# Sitara_Power.net
KiCad netlist of a schematic drawn in Altium Designer
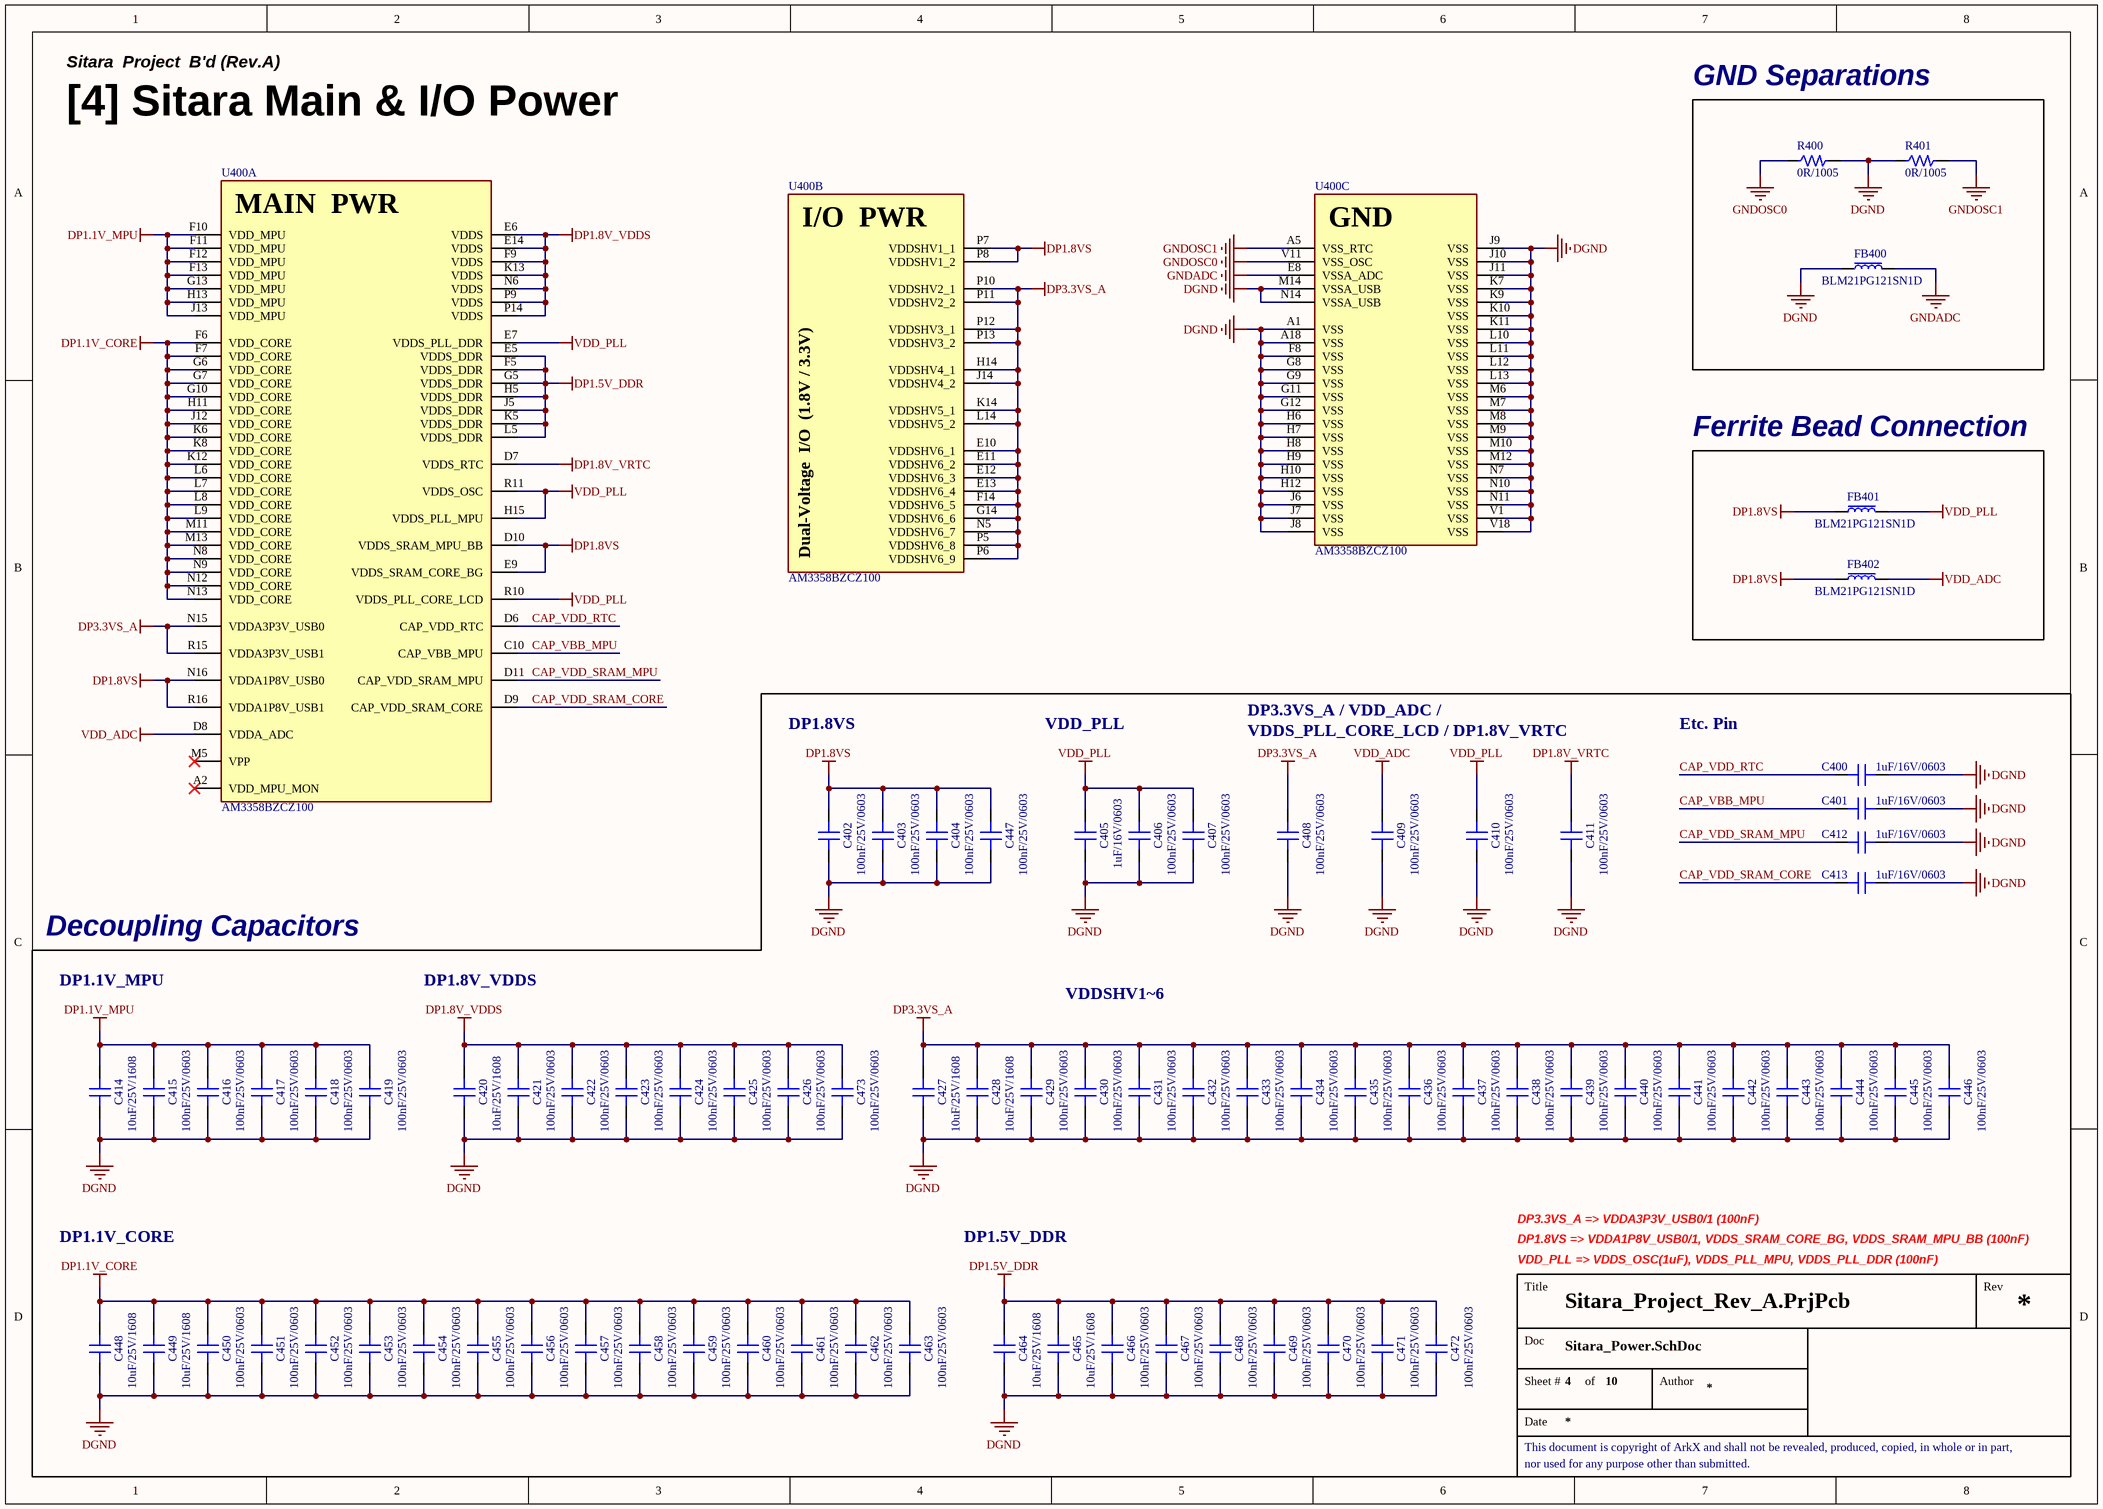
[diagram p0: Sitara_Power.SchDoc]

(export (version "E")
  (design (tool "Eeschema 10.0.6"))
  (components
    (comp (ref "C400")
      (value "1uF/16V/0603")
      (footprint "CAP 0603 (0201_INCH)")
      (description "Ceramic CAP_1uF/16V/0603")
      (fields (field (name "LCSC PART #") "C307385"))
      (libsource (lib "Arkx") (part "CAP_1uF/16V/0603"))
    )
    (comp (ref "C401")
      (value "1uF/16V/0603")
      (footprint "CAP 0603 (0201_INCH)")
      (description "Ceramic CAP_1uF/16V/0603")
      (fields (field (name "LCSC PART #") "C307385"))
      (libsource (lib "Arkx") (part "CAP_1uF/16V/0603"))
    )
    (comp (ref "C402")
      (value "100nF/25V/0603")
      (footprint "CAP 0603 (0201_INCH)")
      (description "Ceramic CAP_100nF/25V/0603")
      (fields (field (name "LCSC PART #") "C181047"))
      (libsource (lib "Arkx") (part "CAP_100nF/25V/0603"))
    )
    (comp (ref "C403")
      (value "100nF/25V/0603")
      (footprint "CAP 0603 (0201_INCH)")
      (description "Ceramic CAP_100nF/25V/0603")
      (fields (field (name "LCSC PART #") "C181047"))
      (libsource (lib "Arkx") (part "CAP_100nF/25V/0603"))
    )
    (comp (ref "C404")
      (value "100nF/25V/0603")
      (footprint "CAP 0603 (0201_INCH)")
      (description "Ceramic CAP_100nF/25V/0603")
      (fields (field (name "LCSC PART #") "C181047"))
      (libsource (lib "Arkx") (part "CAP_100nF/25V/0603"))
    )
    (comp (ref "C405")
      (value "1uF/16V/0603")
      (footprint "CAP 0603 (0201_INCH)")
      (description "Ceramic CAP_1uF/16V/0603")
      (fields (field (name "LCSC PART #") "C307385"))
      (libsource (lib "Arkx") (part "CAP_1uF/16V/0603"))
    )
    (comp (ref "C406")
      (value "100nF/25V/0603")
      (footprint "CAP 0603 (0201_INCH)")
      (description "Ceramic CAP_100nF/25V/0603")
      (fields (field (name "LCSC PART #") "C181047"))
      (libsource (lib "Arkx") (part "CAP_100nF/25V/0603"))
    )
    (comp (ref "C407")
      (value "100nF/25V/0603")
      (footprint "CAP 0603 (0201_INCH)")
      (description "Ceramic CAP_100nF/25V/0603")
      (fields (field (name "LCSC PART #") "C181047"))
      (libsource (lib "Arkx") (part "CAP_100nF/25V/0603"))
    )
    (comp (ref "C408")
      (value "100nF/25V/0603")
      (footprint "CAP 0603 (0201_INCH)")
      (description "Ceramic CAP_100nF/25V/0603")
      (fields (field (name "LCSC PART #") "C181047"))
      (libsource (lib "Arkx") (part "CAP_100nF/25V/0603"))
    )
    (comp (ref "C409")
      (value "100nF/25V/0603")
      (footprint "CAP 0603 (0201_INCH)")
      (description "Ceramic CAP_100nF/25V/0603")
      (fields (field (name "LCSC PART #") "C181047"))
      (libsource (lib "Arkx") (part "CAP_100nF/25V/0603"))
    )
    (comp (ref "C410")
      (value "100nF/25V/0603")
      (footprint "CAP 0603 (0201_INCH)")
      (description "Ceramic CAP_100nF/25V/0603")
      (fields (field (name "LCSC PART #") "C181047"))
      (libsource (lib "Arkx") (part "CAP_100nF/25V/0603"))
    )
    (comp (ref "C411")
      (value "100nF/25V/0603")
      (footprint "CAP 0603 (0201_INCH)")
      (description "Ceramic CAP_100nF/25V/0603")
      (fields (field (name "LCSC PART #") "C181047"))
      (libsource (lib "Arkx") (part "CAP_100nF/25V/0603"))
    )
    (comp (ref "C412")
      (value "1uF/16V/0603")
      (footprint "CAP 0603 (0201_INCH)")
      (description "Ceramic CAP_1uF/16V/0603")
      (fields (field (name "LCSC PART #") "C307385"))
      (libsource (lib "Arkx") (part "CAP_1uF/16V/0603"))
    )
    (comp (ref "C413")
      (value "1uF/16V/0603")
      (footprint "CAP 0603 (0201_INCH)")
      (description "Ceramic CAP_1uF/16V/0603")
      (fields (field (name "LCSC PART #") "C307385"))
      (libsource (lib "Arkx") (part "CAP_1uF/16V/0603"))
    )
    (comp (ref "C414")
      (value "10uF/25V/1608")
      (footprint "CAP 1608 (0603_INCH)")
      (description "Ceramic CAP_10uF/25V/1608")
      (fields (field (name "LCSC PART #") "C96446"))
      (libsource (lib "Arkx") (part "CAP_10uF/25V/1608"))
    )
    (comp (ref "C415")
      (value "100nF/25V/0603")
      (footprint "CAP 0603 (0201_INCH)")
      (description "Ceramic CAP_100nF/25V/0603")
      (fields (field (name "LCSC PART #") "C181047"))
      (libsource (lib "Arkx") (part "CAP_100nF/25V/0603"))
    )
    (comp (ref "C416")
      (value "100nF/25V/0603")
      (footprint "CAP 0603 (0201_INCH)")
      (description "Ceramic CAP_100nF/25V/0603")
      (fields (field (name "LCSC PART #") "C181047"))
      (libsource (lib "Arkx") (part "CAP_100nF/25V/0603"))
    )
    (comp (ref "C417")
      (value "100nF/25V/0603")
      (footprint "CAP 0603 (0201_INCH)")
      (description "Ceramic CAP_100nF/25V/0603")
      (fields (field (name "LCSC PART #") "C181047"))
      (libsource (lib "Arkx") (part "CAP_100nF/25V/0603"))
    )
    (comp (ref "C418")
      (value "100nF/25V/0603")
      (footprint "CAP 0603 (0201_INCH)")
      (description "Ceramic CAP_100nF/25V/0603")
      (fields (field (name "LCSC PART #") "C181047"))
      (libsource (lib "Arkx") (part "CAP_100nF/25V/0603"))
    )
    (comp (ref "C419")
      (value "100nF/25V/0603")
      (footprint "CAP 0603 (0201_INCH)")
      (description "Ceramic CAP_100nF/25V/0603")
      (fields (field (name "LCSC PART #") "C181047"))
      (libsource (lib "Arkx") (part "CAP_100nF/25V/0603"))
    )
    (comp (ref "C420")
      (value "10uF/25V/1608")
      (footprint "CAP 1608 (0603_INCH)")
      (description "Ceramic CAP_10uF/25V/1608")
      (fields (field (name "LCSC PART #") "C96446"))
      (libsource (lib "Arkx") (part "CAP_10uF/25V/1608"))
    )
    (comp (ref "C421")
      (value "100nF/25V/0603")
      (footprint "CAP 0603 (0201_INCH)")
      (description "Ceramic CAP_100nF/25V/0603")
      (fields (field (name "LCSC PART #") "C181047"))
      (libsource (lib "Arkx") (part "CAP_100nF/25V/0603"))
    )
    (comp (ref "C422")
      (value "100nF/25V/0603")
      (footprint "CAP 0603 (0201_INCH)")
      (description "Ceramic CAP_100nF/25V/0603")
      (fields (field (name "LCSC PART #") "C181047"))
      (libsource (lib "Arkx") (part "CAP_100nF/25V/0603"))
    )
    (comp (ref "C423")
      (value "100nF/25V/0603")
      (footprint "CAP 0603 (0201_INCH)")
      (description "Ceramic CAP_100nF/25V/0603")
      (fields (field (name "LCSC PART #") "C181047"))
      (libsource (lib "Arkx") (part "CAP_100nF/25V/0603"))
    )
    (comp (ref "C424")
      (value "100nF/25V/0603")
      (footprint "CAP 0603 (0201_INCH)")
      (description "Ceramic CAP_100nF/25V/0603")
      (fields (field (name "LCSC PART #") "C181047"))
      (libsource (lib "Arkx") (part "CAP_100nF/25V/0603"))
    )
    (comp (ref "C425")
      (value "100nF/25V/0603")
      (footprint "CAP 0603 (0201_INCH)")
      (description "Ceramic CAP_100nF/25V/0603")
      (fields (field (name "LCSC PART #") "C181047"))
      (libsource (lib "Arkx") (part "CAP_100nF/25V/0603"))
    )
    (comp (ref "C426")
      (value "100nF/25V/0603")
      (footprint "CAP 0603 (0201_INCH)")
      (description "Ceramic CAP_100nF/25V/0603")
      (fields (field (name "LCSC PART #") "C181047"))
      (libsource (lib "Arkx") (part "CAP_100nF/25V/0603"))
    )
    (comp (ref "C427")
      (value "10uF/25V/1608")
      (footprint "CAP 1608 (0603_INCH)")
      (description "Ceramic CAP_10uF/25V/1608")
      (fields (field (name "LCSC PART #") "C96446"))
      (libsource (lib "Arkx") (part "CAP_10uF/25V/1608"))
    )
    (comp (ref "C428")
      (value "10uF/25V/1608")
      (footprint "CAP 1608 (0603_INCH)")
      (description "Ceramic CAP_10uF/25V/1608")
      (fields (field (name "LCSC PART #") "C96446"))
      (libsource (lib "Arkx") (part "CAP_10uF/25V/1608"))
    )
    (comp (ref "C429")
      (value "100nF/25V/0603")
      (footprint "CAP 0603 (0201_INCH)")
      (description "Ceramic CAP_100nF/25V/0603")
      (fields (field (name "LCSC PART #") "C181047"))
      (libsource (lib "Arkx") (part "CAP_100nF/25V/0603"))
    )
    (comp (ref "C430")
      (value "100nF/25V/0603")
      (footprint "CAP 0603 (0201_INCH)")
      (description "Ceramic CAP_100nF/25V/0603")
      (fields (field (name "LCSC PART #") "C181047"))
      (libsource (lib "Arkx") (part "CAP_100nF/25V/0603"))
    )
    (comp (ref "C431")
      (value "100nF/25V/0603")
      (footprint "CAP 0603 (0201_INCH)")
      (description "Ceramic CAP_100nF/25V/0603")
      (fields (field (name "LCSC PART #") "C181047"))
      (libsource (lib "Arkx") (part "CAP_100nF/25V/0603"))
    )
    (comp (ref "C432")
      (value "100nF/25V/0603")
      (footprint "CAP 0603 (0201_INCH)")
      (description "Ceramic CAP_100nF/25V/0603")
      (fields (field (name "LCSC PART #") "C181047"))
      (libsource (lib "Arkx") (part "CAP_100nF/25V/0603"))
    )
    (comp (ref "C433")
      (value "100nF/25V/0603")
      (footprint "CAP 0603 (0201_INCH)")
      (description "Ceramic CAP_100nF/25V/0603")
      (fields (field (name "LCSC PART #") "C181047"))
      (libsource (lib "Arkx") (part "CAP_100nF/25V/0603"))
    )
    (comp (ref "C434")
      (value "100nF/25V/0603")
      (footprint "CAP 0603 (0201_INCH)")
      (description "Ceramic CAP_100nF/25V/0603")
      (fields (field (name "LCSC PART #") "C181047"))
      (libsource (lib "Arkx") (part "CAP_100nF/25V/0603"))
    )
    (comp (ref "C435")
      (value "100nF/25V/0603")
      (footprint "CAP 0603 (0201_INCH)")
      (description "Ceramic CAP_100nF/25V/0603")
      (fields (field (name "LCSC PART #") "C181047"))
      (libsource (lib "Arkx") (part "CAP_100nF/25V/0603"))
    )
    (comp (ref "C436")
      (value "100nF/25V/0603")
      (footprint "CAP 0603 (0201_INCH)")
      (description "Ceramic CAP_100nF/25V/0603")
      (fields (field (name "LCSC PART #") "C181047"))
      (libsource (lib "Arkx") (part "CAP_100nF/25V/0603"))
    )
    (comp (ref "C437")
      (value "100nF/25V/0603")
      (footprint "CAP 0603 (0201_INCH)")
      (description "Ceramic CAP_100nF/25V/0603")
      (fields (field (name "LCSC PART #") "C181047"))
      (libsource (lib "Arkx") (part "CAP_100nF/25V/0603"))
    )
    (comp (ref "C438")
      (value "100nF/25V/0603")
      (footprint "CAP 0603 (0201_INCH)")
      (description "Ceramic CAP_100nF/25V/0603")
      (fields (field (name "LCSC PART #") "C181047"))
      (libsource (lib "Arkx") (part "CAP_100nF/25V/0603"))
    )
    (comp (ref "C439")
      (value "100nF/25V/0603")
      (footprint "CAP 0603 (0201_INCH)")
      (description "Ceramic CAP_100nF/25V/0603")
      (fields (field (name "LCSC PART #") "C181047"))
      (libsource (lib "Arkx") (part "CAP_100nF/25V/0603"))
    )
    (comp (ref "C440")
      (value "100nF/25V/0603")
      (footprint "CAP 0603 (0201_INCH)")
      (description "Ceramic CAP_100nF/25V/0603")
      (fields (field (name "LCSC PART #") "C181047"))
      (libsource (lib "Arkx") (part "CAP_100nF/25V/0603"))
    )
    (comp (ref "C441")
      (value "100nF/25V/0603")
      (footprint "CAP 0603 (0201_INCH)")
      (description "Ceramic CAP_100nF/25V/0603")
      (fields (field (name "LCSC PART #") "C181047"))
      (libsource (lib "Arkx") (part "CAP_100nF/25V/0603"))
    )
    (comp (ref "C442")
      (value "100nF/25V/0603")
      (footprint "CAP 0603 (0201_INCH)")
      (description "Ceramic CAP_100nF/25V/0603")
      (fields (field (name "LCSC PART #") "C181047"))
      (libsource (lib "Arkx") (part "CAP_100nF/25V/0603"))
    )
    (comp (ref "C443")
      (value "100nF/25V/0603")
      (footprint "CAP 0603 (0201_INCH)")
      (description "Ceramic CAP_100nF/25V/0603")
      (fields (field (name "LCSC PART #") "C181047"))
      (libsource (lib "Arkx") (part "CAP_100nF/25V/0603"))
    )
    (comp (ref "C444")
      (value "100nF/25V/0603")
      (footprint "CAP 0603 (0201_INCH)")
      (description "Ceramic CAP_100nF/25V/0603")
      (fields (field (name "LCSC PART #") "C181047"))
      (libsource (lib "Arkx") (part "CAP_100nF/25V/0603"))
    )
    (comp (ref "C445")
      (value "100nF/25V/0603")
      (footprint "CAP 0603 (0201_INCH)")
      (description "Ceramic CAP_100nF/25V/0603")
      (fields (field (name "LCSC PART #") "C181047"))
      (libsource (lib "Arkx") (part "CAP_100nF/25V/0603"))
    )
    (comp (ref "C446")
      (value "100nF/25V/0603")
      (footprint "CAP 0603 (0201_INCH)")
      (description "Ceramic CAP_100nF/25V/0603")
      (fields (field (name "LCSC PART #") "C181047"))
      (libsource (lib "Arkx") (part "CAP_100nF/25V/0603"))
    )
    (comp (ref "C447")
      (value "100nF/25V/0603")
      (footprint "CAP 0603 (0201_INCH)")
      (description "Ceramic CAP_100nF/25V/0603")
      (fields (field (name "LCSC PART #") "C181047"))
      (libsource (lib "Arkx") (part "CAP_100nF/25V/0603"))
    )
    (comp (ref "C448")
      (value "10uF/25V/1608")
      (footprint "CAP 1608 (0603_INCH)")
      (description "Ceramic CAP_10uF/25V/1608")
      (fields (field (name "LCSC PART #") "C96446"))
      (libsource (lib "Arkx") (part "CAP_10uF/25V/1608"))
    )
    (comp (ref "C449")
      (value "10uF/25V/1608")
      (footprint "CAP 1608 (0603_INCH)")
      (description "Ceramic CAP_10uF/25V/1608")
      (fields (field (name "LCSC PART #") "C96446"))
      (libsource (lib "Arkx") (part "CAP_10uF/25V/1608"))
    )
    (comp (ref "C450")
      (value "100nF/25V/0603")
      (footprint "CAP 0603 (0201_INCH)")
      (description "Ceramic CAP_100nF/25V/0603")
      (fields (field (name "LCSC PART #") "C181047"))
      (libsource (lib "Arkx") (part "CAP_100nF/25V/0603"))
    )
    (comp (ref "C451")
      (value "100nF/25V/0603")
      (footprint "CAP 0603 (0201_INCH)")
      (description "Ceramic CAP_100nF/25V/0603")
      (fields (field (name "LCSC PART #") "C181047"))
      (libsource (lib "Arkx") (part "CAP_100nF/25V/0603"))
    )
    (comp (ref "C452")
      (value "100nF/25V/0603")
      (footprint "CAP 0603 (0201_INCH)")
      (description "Ceramic CAP_100nF/25V/0603")
      (fields (field (name "LCSC PART #") "C181047"))
      (libsource (lib "Arkx") (part "CAP_100nF/25V/0603"))
    )
    (comp (ref "C453")
      (value "100nF/25V/0603")
      (footprint "CAP 0603 (0201_INCH)")
      (description "Ceramic CAP_100nF/25V/0603")
      (fields (field (name "LCSC PART #") "C181047"))
      (libsource (lib "Arkx") (part "CAP_100nF/25V/0603"))
    )
    (comp (ref "C454")
      (value "100nF/25V/0603")
      (footprint "CAP 0603 (0201_INCH)")
      (description "Ceramic CAP_100nF/25V/0603")
      (fields (field (name "LCSC PART #") "C181047"))
      (libsource (lib "Arkx") (part "CAP_100nF/25V/0603"))
    )
    (comp (ref "C455")
      (value "100nF/25V/0603")
      (footprint "CAP 0603 (0201_INCH)")
      (description "Ceramic CAP_100nF/25V/0603")
      (fields (field (name "LCSC PART #") "C181047"))
      (libsource (lib "Arkx") (part "CAP_100nF/25V/0603"))
    )
    (comp (ref "C456")
      (value "100nF/25V/0603")
      (footprint "CAP 0603 (0201_INCH)")
      (description "Ceramic CAP_100nF/25V/0603")
      (fields (field (name "LCSC PART #") "C181047"))
      (libsource (lib "Arkx") (part "CAP_100nF/25V/0603"))
    )
    (comp (ref "C457")
      (value "100nF/25V/0603")
      (footprint "CAP 0603 (0201_INCH)")
      (description "Ceramic CAP_100nF/25V/0603")
      (fields (field (name "LCSC PART #") "C181047"))
      (libsource (lib "Arkx") (part "CAP_100nF/25V/0603"))
    )
    (comp (ref "C458")
      (value "100nF/25V/0603")
      (footprint "CAP 0603 (0201_INCH)")
      (description "Ceramic CAP_100nF/25V/0603")
      (fields (field (name "LCSC PART #") "C181047"))
      (libsource (lib "Arkx") (part "CAP_100nF/25V/0603"))
    )
    (comp (ref "C459")
      (value "100nF/25V/0603")
      (footprint "CAP 0603 (0201_INCH)")
      (description "Ceramic CAP_100nF/25V/0603")
      (fields (field (name "LCSC PART #") "C181047"))
      (libsource (lib "Arkx") (part "CAP_100nF/25V/0603"))
    )
    (comp (ref "C460")
      (value "100nF/25V/0603")
      (footprint "CAP 0603 (0201_INCH)")
      (description "Ceramic CAP_100nF/25V/0603")
      (fields (field (name "LCSC PART #") "C181047"))
      (libsource (lib "Arkx") (part "CAP_100nF/25V/0603"))
    )
    (comp (ref "C461")
      (value "100nF/25V/0603")
      (footprint "CAP 0603 (0201_INCH)")
      (description "Ceramic CAP_100nF/25V/0603")
      (fields (field (name "LCSC PART #") "C181047"))
      (libsource (lib "Arkx") (part "CAP_100nF/25V/0603"))
    )
    (comp (ref "C462")
      (value "100nF/25V/0603")
      (footprint "CAP 0603 (0201_INCH)")
      (description "Ceramic CAP_100nF/25V/0603")
      (fields (field (name "LCSC PART #") "C181047"))
      (libsource (lib "Arkx") (part "CAP_100nF/25V/0603"))
    )
    (comp (ref "C463")
      (value "100nF/25V/0603")
      (footprint "CAP 0603 (0201_INCH)")
      (description "Ceramic CAP_100nF/25V/0603")
      (fields (field (name "LCSC PART #") "C181047"))
      (libsource (lib "Arkx") (part "CAP_100nF/25V/0603"))
    )
    (comp (ref "C464")
      (value "10uF/25V/1608")
      (footprint "CAP 1608 (0603_INCH)")
      (description "Ceramic CAP_10uF/25V/1608")
      (fields (field (name "LCSC PART #") "C96446"))
      (libsource (lib "Arkx") (part "CAP_10uF/25V/1608"))
    )
    (comp (ref "C465")
      (value "10uF/25V/1608")
      (footprint "CAP 1608 (0603_INCH)")
      (description "Ceramic CAP_10uF/25V/1608")
      (fields (field (name "LCSC PART #") "C96446"))
      (libsource (lib "Arkx") (part "CAP_10uF/25V/1608"))
    )
    (comp (ref "C466")
      (value "100nF/25V/0603")
      (footprint "CAP 0603 (0201_INCH)")
      (description "Ceramic CAP_100nF/25V/0603")
      (fields (field (name "LCSC PART #") "C181047"))
      (libsource (lib "Arkx") (part "CAP_100nF/25V/0603"))
    )
    (comp (ref "C467")
      (value "100nF/25V/0603")
      (footprint "CAP 0603 (0201_INCH)")
      (description "Ceramic CAP_100nF/25V/0603")
      (fields (field (name "LCSC PART #") "C181047"))
      (libsource (lib "Arkx") (part "CAP_100nF/25V/0603"))
    )
    (comp (ref "C468")
      (value "100nF/25V/0603")
      (footprint "CAP 0603 (0201_INCH)")
      (description "Ceramic CAP_100nF/25V/0603")
      (fields (field (name "LCSC PART #") "C181047"))
      (libsource (lib "Arkx") (part "CAP_100nF/25V/0603"))
    )
    (comp (ref "C469")
      (value "100nF/25V/0603")
      (footprint "CAP 0603 (0201_INCH)")
      (description "Ceramic CAP_100nF/25V/0603")
      (fields (field (name "LCSC PART #") "C181047"))
      (libsource (lib "Arkx") (part "CAP_100nF/25V/0603"))
    )
    (comp (ref "C470")
      (value "100nF/25V/0603")
      (footprint "CAP 0603 (0201_INCH)")
      (description "Ceramic CAP_100nF/25V/0603")
      (fields (field (name "LCSC PART #") "C181047"))
      (libsource (lib "Arkx") (part "CAP_100nF/25V/0603"))
    )
    (comp (ref "C471")
      (value "100nF/25V/0603")
      (footprint "CAP 0603 (0201_INCH)")
      (description "Ceramic CAP_100nF/25V/0603")
      (fields (field (name "LCSC PART #") "C181047"))
      (libsource (lib "Arkx") (part "CAP_100nF/25V/0603"))
    )
    (comp (ref "C472")
      (value "100nF/25V/0603")
      (footprint "CAP 0603 (0201_INCH)")
      (description "Ceramic CAP_100nF/25V/0603")
      (fields (field (name "LCSC PART #") "C181047"))
      (libsource (lib "Arkx") (part "CAP_100nF/25V/0603"))
    )
    (comp (ref "C473")
      (value "100nF/25V/0603")
      (footprint "CAP 0603 (0201_INCH)")
      (description "Ceramic CAP_100nF/25V/0603")
      (fields (field (name "LCSC PART #") "C181047"))
      (libsource (lib "Arkx") (part "CAP_100nF/25V/0603"))
    )
    (comp (ref "FB400")
      (value "BLM21PG121SN1D")
      (footprint "FB 2012 (0805_inch)")
      (description "3A 1 30mΩ 120Ω@100MHz ±25% 0805  Ferrite Beads ROHS")
      (fields (field (name "LCSC PART #") "C79382"))
      (libsource (lib "Arkx") (part "FB_BLM21PG121SN1D"))
    )
    (comp (ref "FB401")
      (value "BLM21PG121SN1D")
      (footprint "FB 2012 (0805_inch)")
      (description "3A 1 30mΩ 120Ω@100MHz ±25% 0805  Ferrite Beads ROHS")
      (fields (field (name "LCSC PART #") "C79382"))
      (libsource (lib "Arkx") (part "FB_BLM21PG121SN1D"))
    )
    (comp (ref "FB402")
      (value "BLM21PG121SN1D")
      (footprint "FB 2012 (0805_inch)")
      (description "3A 1 30mΩ 120Ω@100MHz ±25% 0805  Ferrite Beads ROHS")
      (fields (field (name "LCSC PART #") "C79382"))
      (libsource (lib "Arkx") (part "FB_BLM21PG121SN1D"))
    )
    (comp (ref "R400")
      (value "0R/1005")
      (footprint "RES 1005 (0402_inch)")
      (description "RES_0R/1005/62.5mW")
      (fields (field (name "LCSC PART #") "C17168"))
      (libsource (lib "Arkx") (part "RES_0R/1005/62.5mW"))
    )
    (comp (ref "R401")
      (value "0R/1005")
      (footprint "RES 1005 (0402_inch)")
      (description "RES_0R/1005/62.5mW")
      (fields (field (name "LCSC PART #") "C17168"))
      (libsource (lib "Arkx") (part "RES_0R/1005/62.5mW"))
    )
    (comp (ref "U400")
      (value "AM3358BZCZ100")
      (footprint "IC_SOC_AM3358BZCZ100")
      (description "ARM® Cortex®-A8 Microprocessor IC Sitara™ 1 Core, 32-Bit 1.0GHz 324-NFBGA (15x15)")
      (fields (field (name "LCSC PART #") "C73932"))
      (libsource (lib "Arkx") (part "IC_SOC_AM3358BZCZ100"))
    )
  )
  (nets
    (net (code "1") (name "/CAP_VBB_MPU") (class "Default")
      (node (ref "C401") (pin "1") (pinfunction "1_1") (pintype "passive"))
      (node (ref "U400") (pin "C10") (pinfunction "CAP_VBB_MPU_C10") (pintype "power_in"))
    )
    (net (code "2") (name "/CAP_VDD_RTC") (class "Default")
      (node (ref "C400") (pin "1") (pinfunction "1_1") (pintype "passive"))
      (node (ref "U400") (pin "D6") (pinfunction "CAP_VDD_RTC_D6") (pintype "power_in"))
    )
    (net (code "3") (name "/CAP_VDD_SRAM_CORE") (class "Default")
      (node (ref "C413") (pin "1") (pinfunction "1_1") (pintype "passive"))
      (node (ref "U400") (pin "D9") (pinfunction "CAP_VDD_SRAM_CORE_D9") (pintype "power_in"))
    )
    (net (code "4") (name "/CAP_VDD_SRAM_MPU") (class "Default")
      (node (ref "C412") (pin "1") (pinfunction "1_1") (pintype "passive"))
      (node (ref "U400") (pin "D11") (pinfunction "CAP_VDD_SRAM_MPU_D11") (pintype "power_in"))
    )
    (net (code "5") (name "DGND") (class "Default")
      (node (ref "C400") (pin "2") (pinfunction "2_2") (pintype "passive"))
      (node (ref "C401") (pin "2") (pinfunction "2_2") (pintype "passive"))
      (node (ref "C402") (pin "1") (pinfunction "1_1") (pintype "passive"))
      (node (ref "C403") (pin "1") (pinfunction "1_1") (pintype "passive"))
      (node (ref "C404") (pin "1") (pinfunction "1_1") (pintype "passive"))
      (node (ref "C405") (pin "1") (pinfunction "1_1") (pintype "passive"))
      (node (ref "C406") (pin "1") (pinfunction "1_1") (pintype "passive"))
      (node (ref "C407") (pin "1") (pinfunction "1_1") (pintype "passive"))
      (node (ref "C408") (pin "1") (pinfunction "1_1") (pintype "passive"))
      (node (ref "C409") (pin "1") (pinfunction "1_1") (pintype "passive"))
      (node (ref "C410") (pin "1") (pinfunction "1_1") (pintype "passive"))
      (node (ref "C411") (pin "1") (pinfunction "1_1") (pintype "passive"))
      (node (ref "C412") (pin "2") (pinfunction "2_2") (pintype "passive"))
      (node (ref "C413") (pin "2") (pinfunction "2_2") (pintype "passive"))
      (node (ref "C414") (pin "1") (pinfunction "1_1") (pintype "passive"))
      (node (ref "C415") (pin "1") (pinfunction "1_1") (pintype "passive"))
      (node (ref "C416") (pin "1") (pinfunction "1_1") (pintype "passive"))
      (node (ref "C417") (pin "1") (pinfunction "1_1") (pintype "passive"))
      (node (ref "C418") (pin "1") (pinfunction "1_1") (pintype "passive"))
      (node (ref "C419") (pin "1") (pinfunction "1_1") (pintype "passive"))
      (node (ref "C420") (pin "1") (pinfunction "1_1") (pintype "passive"))
      (node (ref "C421") (pin "1") (pinfunction "1_1") (pintype "passive"))
      (node (ref "C422") (pin "1") (pinfunction "1_1") (pintype "passive"))
      (node (ref "C423") (pin "1") (pinfunction "1_1") (pintype "passive"))
      (node (ref "C424") (pin "1") (pinfunction "1_1") (pintype "passive"))
      (node (ref "C425") (pin "1") (pinfunction "1_1") (pintype "passive"))
      (node (ref "C426") (pin "1") (pinfunction "1_1") (pintype "passive"))
      (node (ref "C427") (pin "1") (pinfunction "1_1") (pintype "passive"))
      (node (ref "C428") (pin "1") (pinfunction "1_1") (pintype "passive"))
      (node (ref "C429") (pin "1") (pinfunction "1_1") (pintype "passive"))
      (node (ref "C430") (pin "1") (pinfunction "1_1") (pintype "passive"))
      (node (ref "C431") (pin "1") (pinfunction "1_1") (pintype "passive"))
      (node (ref "C432") (pin "1") (pinfunction "1_1") (pintype "passive"))
      (node (ref "C433") (pin "1") (pinfunction "1_1") (pintype "passive"))
      (node (ref "C434") (pin "1") (pinfunction "1_1") (pintype "passive"))
      (node (ref "C435") (pin "1") (pinfunction "1_1") (pintype "passive"))
      (node (ref "C436") (pin "1") (pinfunction "1_1") (pintype "passive"))
      (node (ref "C437") (pin "1") (pinfunction "1_1") (pintype "passive"))
      (node (ref "C438") (pin "1") (pinfunction "1_1") (pintype "passive"))
      (node (ref "C439") (pin "1") (pinfunction "1_1") (pintype "passive"))
      (node (ref "C440") (pin "1") (pinfunction "1_1") (pintype "passive"))
      (node (ref "C441") (pin "1") (pinfunction "1_1") (pintype "passive"))
      (node (ref "C442") (pin "1") (pinfunction "1_1") (pintype "passive"))
      (node (ref "C443") (pin "1") (pinfunction "1_1") (pintype "passive"))
      (node (ref "C444") (pin "1") (pinfunction "1_1") (pintype "passive"))
      (node (ref "C445") (pin "1") (pinfunction "1_1") (pintype "passive"))
      (node (ref "C446") (pin "1") (pinfunction "1_1") (pintype "passive"))
      (node (ref "C447") (pin "1") (pinfunction "1_1") (pintype "passive"))
      (node (ref "C448") (pin "1") (pinfunction "1_1") (pintype "passive"))
      (node (ref "C449") (pin "1") (pinfunction "1_1") (pintype "passive"))
      (node (ref "C450") (pin "1") (pinfunction "1_1") (pintype "passive"))
      (node (ref "C451") (pin "1") (pinfunction "1_1") (pintype "passive"))
      (node (ref "C452") (pin "1") (pinfunction "1_1") (pintype "passive"))
      (node (ref "C453") (pin "1") (pinfunction "1_1") (pintype "passive"))
      (node (ref "C454") (pin "1") (pinfunction "1_1") (pintype "passive"))
      (node (ref "C455") (pin "1") (pinfunction "1_1") (pintype "passive"))
      (node (ref "C456") (pin "1") (pinfunction "1_1") (pintype "passive"))
      (node (ref "C457") (pin "1") (pinfunction "1_1") (pintype "passive"))
      (node (ref "C458") (pin "1") (pinfunction "1_1") (pintype "passive"))
      (node (ref "C459") (pin "1") (pinfunction "1_1") (pintype "passive"))
      (node (ref "C460") (pin "1") (pinfunction "1_1") (pintype "passive"))
      (node (ref "C461") (pin "1") (pinfunction "1_1") (pintype "passive"))
      (node (ref "C462") (pin "1") (pinfunction "1_1") (pintype "passive"))
      (node (ref "C463") (pin "1") (pinfunction "1_1") (pintype "passive"))
      (node (ref "C464") (pin "1") (pinfunction "1_1") (pintype "passive"))
      (node (ref "C465") (pin "1") (pinfunction "1_1") (pintype "passive"))
      (node (ref "C466") (pin "1") (pinfunction "1_1") (pintype "passive"))
      (node (ref "C467") (pin "1") (pinfunction "1_1") (pintype "passive"))
      (node (ref "C468") (pin "1") (pinfunction "1_1") (pintype "passive"))
      (node (ref "C469") (pin "1") (pinfunction "1_1") (pintype "passive"))
      (node (ref "C470") (pin "1") (pinfunction "1_1") (pintype "passive"))
      (node (ref "C471") (pin "1") (pinfunction "1_1") (pintype "passive"))
      (node (ref "C472") (pin "1") (pinfunction "1_1") (pintype "passive"))
      (node (ref "C473") (pin "1") (pinfunction "1_1") (pintype "passive"))
      (node (ref "FB400") (pin "1") (pinfunction "1_1") (pintype "passive"))
      (node (ref "R400") (pin "2") (pinfunction "2_2") (pintype "passive"))
      (node (ref "R401") (pin "1") (pinfunction "1_1") (pintype "passive"))
      (node (ref "U400") (pin "A1") (pinfunction "VSS_A1") (pintype "power_in"))
      (node (ref "U400") (pin "A18") (pinfunction "VSS_A18") (pintype "power_in"))
      (node (ref "U400") (pin "F8") (pinfunction "VSS_F8") (pintype "power_in"))
      (node (ref "U400") (pin "G11") (pinfunction "VSS_G11") (pintype "power_in"))
      (node (ref "U400") (pin "G12") (pinfunction "VSS_G12") (pintype "power_in"))
      (node (ref "U400") (pin "G8") (pinfunction "VSS_G8") (pintype "power_in"))
      (node (ref "U400") (pin "G9") (pinfunction "VSS_G9") (pintype "power_in"))
      (node (ref "U400") (pin "H10") (pinfunction "VSS_H10") (pintype "power_in"))
      (node (ref "U400") (pin "H12") (pinfunction "VSS_H12") (pintype "power_in"))
      (node (ref "U400") (pin "H6") (pinfunction "VSS_H6") (pintype "power_in"))
      (node (ref "U400") (pin "H7") (pinfunction "VSS_H7") (pintype "power_in"))
      (node (ref "U400") (pin "H8") (pinfunction "VSS_H8") (pintype "power_in"))
      (node (ref "U400") (pin "H9") (pinfunction "VSS_H9") (pintype "power_in"))
      (node (ref "U400") (pin "J10") (pinfunction "VSS_J10") (pintype "power_in"))
      (node (ref "U400") (pin "J11") (pinfunction "VSS_J11") (pintype "power_in"))
      (node (ref "U400") (pin "J6") (pinfunction "VSS_J6") (pintype "power_in"))
      (node (ref "U400") (pin "J7") (pinfunction "VSS_J7") (pintype "power_in"))
      (node (ref "U400") (pin "J8") (pinfunction "VSS_J8") (pintype "power_in"))
      (node (ref "U400") (pin "J9") (pinfunction "VSS_J9") (pintype "power_in"))
      (node (ref "U400") (pin "K10") (pinfunction "VSS_K10") (pintype "power_in"))
      (node (ref "U400") (pin "K11") (pinfunction "VSS_K11") (pintype "power_in"))
      (node (ref "U400") (pin "K7") (pinfunction "VSS_K7") (pintype "power_in"))
      (node (ref "U400") (pin "K9") (pinfunction "VSS_K9") (pintype "power_in"))
      (node (ref "U400") (pin "L10") (pinfunction "VSS_L10") (pintype "power_in"))
      (node (ref "U400") (pin "L11") (pinfunction "VSS_L11") (pintype "power_in"))
      (node (ref "U400") (pin "L12") (pinfunction "VSS_L12") (pintype "power_in"))
      (node (ref "U400") (pin "L13") (pinfunction "VSS_L13") (pintype "power_in"))
      (node (ref "U400") (pin "M10") (pinfunction "VSS_M10") (pintype "power_in"))
      (node (ref "U400") (pin "M12") (pinfunction "VSS_M12") (pintype "power_in"))
      (node (ref "U400") (pin "M14") (pinfunction "VSSA_USB_M14") (pintype "power_in"))
      (node (ref "U400") (pin "M6") (pinfunction "VSS_M6") (pintype "power_in"))
      (node (ref "U400") (pin "M7") (pinfunction "VSS_M7") (pintype "power_in"))
      (node (ref "U400") (pin "M8") (pinfunction "VSS_M8") (pintype "power_in"))
      (node (ref "U400") (pin "M9") (pinfunction "VSS_M9") (pintype "power_in"))
      (node (ref "U400") (pin "N10") (pinfunction "VSS_N10") (pintype "power_in"))
      (node (ref "U400") (pin "N11") (pinfunction "VSS_N11") (pintype "power_in"))
      (node (ref "U400") (pin "N14") (pinfunction "VSSA_USB_N14") (pintype "power_in"))
      (node (ref "U400") (pin "N7") (pinfunction "VSS_N7") (pintype "power_in"))
      (node (ref "U400") (pin "V1") (pinfunction "VSS_V1") (pintype "power_in"))
      (node (ref "U400") (pin "V18") (pinfunction "VSS_V18") (pintype "power_in"))
    )
    (net (code "6") (name "DP1.1V_CORE") (class "Default")
      (node (ref "C448") (pin "2") (pinfunction "2_2") (pintype "passive"))
      (node (ref "C449") (pin "2") (pinfunction "2_2") (pintype "passive"))
      (node (ref "C450") (pin "2") (pinfunction "2_2") (pintype "passive"))
      (node (ref "C451") (pin "2") (pinfunction "2_2") (pintype "passive"))
      (node (ref "C452") (pin "2") (pinfunction "2_2") (pintype "passive"))
      (node (ref "C453") (pin "2") (pinfunction "2_2") (pintype "passive"))
      (node (ref "C454") (pin "2") (pinfunction "2_2") (pintype "passive"))
      (node (ref "C455") (pin "2") (pinfunction "2_2") (pintype "passive"))
      (node (ref "C456") (pin "2") (pinfunction "2_2") (pintype "passive"))
      (node (ref "C457") (pin "2") (pinfunction "2_2") (pintype "passive"))
      (node (ref "C458") (pin "2") (pinfunction "2_2") (pintype "passive"))
      (node (ref "C459") (pin "2") (pinfunction "2_2") (pintype "passive"))
      (node (ref "C460") (pin "2") (pinfunction "2_2") (pintype "passive"))
      (node (ref "C461") (pin "2") (pinfunction "2_2") (pintype "passive"))
      (node (ref "C462") (pin "2") (pinfunction "2_2") (pintype "passive"))
      (node (ref "C463") (pin "2") (pinfunction "2_2") (pintype "passive"))
      (node (ref "U400") (pin "F6") (pinfunction "VDD_CORE_F6") (pintype "power_in"))
      (node (ref "U400") (pin "F7") (pinfunction "VDD_CORE_F7") (pintype "power_in"))
      (node (ref "U400") (pin "G10") (pinfunction "VDD_CORE_G10") (pintype "power_in"))
      (node (ref "U400") (pin "G6") (pinfunction "VDD_CORE_G6") (pintype "power_in"))
      (node (ref "U400") (pin "G7") (pinfunction "VDD_CORE_G7") (pintype "power_in"))
      (node (ref "U400") (pin "H11") (pinfunction "VDD_CORE_H11") (pintype "power_in"))
      (node (ref "U400") (pin "J12") (pinfunction "VDD_CORE_J12") (pintype "power_in"))
      (node (ref "U400") (pin "K12") (pinfunction "VDD_CORE_K12") (pintype "power_in"))
      (node (ref "U400") (pin "K6") (pinfunction "VDD_CORE_K6") (pintype "power_in"))
      (node (ref "U400") (pin "K8") (pinfunction "VDD_CORE_K8") (pintype "power_in"))
      (node (ref "U400") (pin "L6") (pinfunction "VDD_CORE_L6") (pintype "power_in"))
      (node (ref "U400") (pin "L7") (pinfunction "VDD_CORE_L7") (pintype "power_in"))
      (node (ref "U400") (pin "L8") (pinfunction "VDD_CORE_L8") (pintype "power_in"))
      (node (ref "U400") (pin "L9") (pinfunction "VDD_CORE_L9") (pintype "power_in"))
      (node (ref "U400") (pin "M11") (pinfunction "VDD_CORE_M11") (pintype "power_in"))
      (node (ref "U400") (pin "M13") (pinfunction "VDD_CORE_M13") (pintype "power_in"))
      (node (ref "U400") (pin "N12") (pinfunction "VDD_CORE_N12") (pintype "power_in"))
      (node (ref "U400") (pin "N13") (pinfunction "VDD_CORE_N13") (pintype "power_in"))
      (node (ref "U400") (pin "N8") (pinfunction "VDD_CORE_N8") (pintype "power_in"))
      (node (ref "U400") (pin "N9") (pinfunction "VDD_CORE_N9") (pintype "power_in"))
    )
    (net (code "7") (name "DP1.1V_MPU") (class "Default")
      (node (ref "C414") (pin "2") (pinfunction "2_2") (pintype "passive"))
      (node (ref "C415") (pin "2") (pinfunction "2_2") (pintype "passive"))
      (node (ref "C416") (pin "2") (pinfunction "2_2") (pintype "passive"))
      (node (ref "C417") (pin "2") (pinfunction "2_2") (pintype "passive"))
      (node (ref "C418") (pin "2") (pinfunction "2_2") (pintype "passive"))
      (node (ref "C419") (pin "2") (pinfunction "2_2") (pintype "passive"))
      (node (ref "U400") (pin "F10") (pinfunction "VDD_MPU_F10") (pintype "power_in"))
      (node (ref "U400") (pin "F11") (pinfunction "VDD_MPU_F11") (pintype "power_in"))
      (node (ref "U400") (pin "F12") (pinfunction "VDD_MPU_F12") (pintype "power_in"))
      (node (ref "U400") (pin "F13") (pinfunction "VDD_MPU_F13") (pintype "power_in"))
      (node (ref "U400") (pin "G13") (pinfunction "VDD_MPU_G13") (pintype "power_in"))
      (node (ref "U400") (pin "H13") (pinfunction "VDD_MPU_H13") (pintype "power_in"))
      (node (ref "U400") (pin "J13") (pinfunction "VDD_MPU_J13") (pintype "power_in"))
    )
    (net (code "8") (name "DP1.5V_DDR") (class "Default")
      (node (ref "C464") (pin "2") (pinfunction "2_2") (pintype "passive"))
      (node (ref "C465") (pin "2") (pinfunction "2_2") (pintype "passive"))
      (node (ref "C466") (pin "2") (pinfunction "2_2") (pintype "passive"))
      (node (ref "C467") (pin "2") (pinfunction "2_2") (pintype "passive"))
      (node (ref "C468") (pin "2") (pinfunction "2_2") (pintype "passive"))
      (node (ref "C469") (pin "2") (pinfunction "2_2") (pintype "passive"))
      (node (ref "C470") (pin "2") (pinfunction "2_2") (pintype "passive"))
      (node (ref "C471") (pin "2") (pinfunction "2_2") (pintype "passive"))
      (node (ref "C472") (pin "2") (pinfunction "2_2") (pintype "passive"))
      (node (ref "U400") (pin "E5") (pinfunction "VDDS_DDR_E5") (pintype "power_in"))
      (node (ref "U400") (pin "F5") (pinfunction "VDDS_DDR_F5") (pintype "power_in"))
      (node (ref "U400") (pin "G5") (pinfunction "VDDS_DDR_G5") (pintype "power_in"))
      (node (ref "U400") (pin "H5") (pinfunction "VDDS_DDR_H5") (pintype "power_in"))
      (node (ref "U400") (pin "J5") (pinfunction "VDDS_DDR_J5") (pintype "power_in"))
      (node (ref "U400") (pin "K5") (pinfunction "VDDS_DDR_K5") (pintype "power_in"))
      (node (ref "U400") (pin "L5") (pinfunction "VDDS_DDR_L5") (pintype "power_in"))
    )
    (net (code "9") (name "DP1.8VS") (class "Default")
      (node (ref "C402") (pin "2") (pinfunction "2_2") (pintype "passive"))
      (node (ref "C403") (pin "2") (pinfunction "2_2") (pintype "passive"))
      (node (ref "C404") (pin "2") (pinfunction "2_2") (pintype "passive"))
      (node (ref "C447") (pin "2") (pinfunction "2_2") (pintype "passive"))
      (node (ref "FB401") (pin "1") (pinfunction "1_1") (pintype "passive"))
      (node (ref "FB402") (pin "1") (pinfunction "1_1") (pintype "passive"))
      (node (ref "U400") (pin "D10") (pinfunction "VDDS_SRAM_MPU_BB_D10") (pintype "power_in"))
      (node (ref "U400") (pin "E9") (pinfunction "VDDS_SRAM_CORE_BG_E9") (pintype "power_in"))
      (node (ref "U400") (pin "N16") (pinfunction "VDDA1P8V_USB0_N16") (pintype "power_in"))
      (node (ref "U400") (pin "P7") (pinfunction "VDDSHV1_1_P7") (pintype "power_in"))
      (node (ref "U400") (pin "P8") (pinfunction "VDDSHV1_2_P8") (pintype "power_in"))
      (node (ref "U400") (pin "R16") (pinfunction "VDDA1P8V_USB1_R16") (pintype "power_in"))
    )
    (net (code "10") (name "DP1.8V_VDDS") (class "Default")
      (node (ref "C420") (pin "2") (pinfunction "2_2") (pintype "passive"))
      (node (ref "C421") (pin "2") (pinfunction "2_2") (pintype "passive"))
      (node (ref "C422") (pin "2") (pinfunction "2_2") (pintype "passive"))
      (node (ref "C423") (pin "2") (pinfunction "2_2") (pintype "passive"))
      (node (ref "C424") (pin "2") (pinfunction "2_2") (pintype "passive"))
      (node (ref "C425") (pin "2") (pinfunction "2_2") (pintype "passive"))
      (node (ref "C426") (pin "2") (pinfunction "2_2") (pintype "passive"))
      (node (ref "C473") (pin "2") (pinfunction "2_2") (pintype "passive"))
      (node (ref "U400") (pin "E14") (pinfunction "VDDS_E14") (pintype "power_in"))
      (node (ref "U400") (pin "E6") (pinfunction "VDDS_E6") (pintype "power_in"))
      (node (ref "U400") (pin "F9") (pinfunction "VDDS_F9") (pintype "power_in"))
      (node (ref "U400") (pin "K13") (pinfunction "VDDS_K13") (pintype "power_in"))
      (node (ref "U400") (pin "N6") (pinfunction "VDDS_N6") (pintype "power_in"))
      (node (ref "U400") (pin "P14") (pinfunction "VDDS_P14") (pintype "power_in"))
      (node (ref "U400") (pin "P9") (pinfunction "VDDS_P9") (pintype "power_in"))
    )
    (net (code "11") (name "DP1.8V_VRTC") (class "Default")
      (node (ref "C411") (pin "2") (pinfunction "2_2") (pintype "passive"))
      (node (ref "U400") (pin "D7") (pinfunction "VDDS_RTC_D7") (pintype "power_in"))
    )
    (net (code "12") (name "DP3.3VS_A") (class "Default")
      (node (ref "C408") (pin "2") (pinfunction "2_2") (pintype "passive"))
      (node (ref "C427") (pin "2") (pinfunction "2_2") (pintype "passive"))
      (node (ref "C428") (pin "2") (pinfunction "2_2") (pintype "passive"))
      (node (ref "C429") (pin "2") (pinfunction "2_2") (pintype "passive"))
      (node (ref "C430") (pin "2") (pinfunction "2_2") (pintype "passive"))
      (node (ref "C431") (pin "2") (pinfunction "2_2") (pintype "passive"))
      (node (ref "C432") (pin "2") (pinfunction "2_2") (pintype "passive"))
      (node (ref "C433") (pin "2") (pinfunction "2_2") (pintype "passive"))
      (node (ref "C434") (pin "2") (pinfunction "2_2") (pintype "passive"))
      (node (ref "C435") (pin "2") (pinfunction "2_2") (pintype "passive"))
      (node (ref "C436") (pin "2") (pinfunction "2_2") (pintype "passive"))
      (node (ref "C437") (pin "2") (pinfunction "2_2") (pintype "passive"))
      (node (ref "C438") (pin "2") (pinfunction "2_2") (pintype "passive"))
      (node (ref "C439") (pin "2") (pinfunction "2_2") (pintype "passive"))
      (node (ref "C440") (pin "2") (pinfunction "2_2") (pintype "passive"))
      (node (ref "C441") (pin "2") (pinfunction "2_2") (pintype "passive"))
      (node (ref "C442") (pin "2") (pinfunction "2_2") (pintype "passive"))
      (node (ref "C443") (pin "2") (pinfunction "2_2") (pintype "passive"))
      (node (ref "C444") (pin "2") (pinfunction "2_2") (pintype "passive"))
      (node (ref "C445") (pin "2") (pinfunction "2_2") (pintype "passive"))
      (node (ref "C446") (pin "2") (pinfunction "2_2") (pintype "passive"))
      (node (ref "U400") (pin "E10") (pinfunction "VDDSHV6_1_E10") (pintype "power_in"))
      (node (ref "U400") (pin "E11") (pinfunction "VDDSHV6_2_E11") (pintype "power_in"))
      (node (ref "U400") (pin "E12") (pinfunction "VDDSHV6_3_E12") (pintype "power_in"))
      (node (ref "U400") (pin "E13") (pinfunction "VDDSHV6_4_E13") (pintype "power_in"))
      (node (ref "U400") (pin "F14") (pinfunction "VDDSHV6_5_F14") (pintype "power_in"))
      (node (ref "U400") (pin "G14") (pinfunction "VDDSHV6_6_G14") (pintype "power_in"))
      (node (ref "U400") (pin "H14") (pinfunction "VDDSHV4_1_H14") (pintype "power_in"))
      (node (ref "U400") (pin "J14") (pinfunction "VDDSHV4_2_J14") (pintype "power_in"))
      (node (ref "U400") (pin "K14") (pinfunction "VDDSHV5_1_K14") (pintype "power_in"))
      (node (ref "U400") (pin "L14") (pinfunction "VDDSHV5_2_L14") (pintype "power_in"))
      (node (ref "U400") (pin "N15") (pinfunction "VDDA3P3V_USB0_N15") (pintype "power_in"))
      (node (ref "U400") (pin "N5") (pinfunction "VDDSHV6_7_N5") (pintype "power_in"))
      (node (ref "U400") (pin "P10") (pinfunction "VDDSHV2_1_P10") (pintype "power_in"))
      (node (ref "U400") (pin "P11") (pinfunction "VDDSHV2_2_P11") (pintype "power_in"))
      (node (ref "U400") (pin "P12") (pinfunction "VDDSHV3_1_P12") (pintype "power_in"))
      (node (ref "U400") (pin "P13") (pinfunction "VDDSHV3_2_P13") (pintype "power_in"))
      (node (ref "U400") (pin "P5") (pinfunction "VDDSHV6_8_P5") (pintype "power_in"))
      (node (ref "U400") (pin "P6") (pinfunction "VDDSHV6_9_P6") (pintype "power_in"))
      (node (ref "U400") (pin "R15") (pinfunction "VDDA3P3V_USB1_R15") (pintype "power_in"))
    )
    (net (code "13") (name "GNDADC") (class "Default")
      (node (ref "FB400") (pin "2") (pinfunction "2_2") (pintype "passive"))
      (node (ref "U400") (pin "E8") (pinfunction "VSSA_ADC_E8") (pintype "power_in"))
    )
    (net (code "14") (name "GNDOSC0") (class "Default")
      (node (ref "R400") (pin "1") (pinfunction "1_1") (pintype "passive"))
      (node (ref "U400") (pin "V11") (pinfunction "VSS_OSC_V11") (pintype "power_in"))
    )
    (net (code "15") (name "GNDOSC1") (class "Default")
      (node (ref "R401") (pin "2") (pinfunction "2_2") (pintype "passive"))
      (node (ref "U400") (pin "A5") (pinfunction "VSS_RTC_A5") (pintype "power_in"))
    )
    (net (code "16") (name "VDD_ADC") (class "Default")
      (node (ref "C409") (pin "2") (pinfunction "2_2") (pintype "passive"))
      (node (ref "FB402") (pin "2") (pinfunction "2_2") (pintype "passive"))
      (node (ref "U400") (pin "D8") (pinfunction "VDDA_ADC_D8") (pintype "power_in"))
    )
    (net (code "17") (name "VDD_PLL") (class "Default")
      (node (ref "C405") (pin "2") (pinfunction "2_2") (pintype "passive"))
      (node (ref "C406") (pin "2") (pinfunction "2_2") (pintype "passive"))
      (node (ref "C407") (pin "2") (pinfunction "2_2") (pintype "passive"))
      (node (ref "C410") (pin "2") (pinfunction "2_2") (pintype "passive"))
      (node (ref "FB401") (pin "2") (pinfunction "2_2") (pintype "passive"))
      (node (ref "U400") (pin "E7") (pinfunction "VDDS_PLL_DDR_E7") (pintype "power_in"))
      (node (ref "U400") (pin "H15") (pinfunction "VDDS_PLL_MPU_H15") (pintype "power_in"))
      (node (ref "U400") (pin "R10") (pinfunction "VDDS_PLL_CORE_LCD_R10") (pintype "power_in"))
      (node (ref "U400") (pin "R11") (pinfunction "VDDS_OSC_R11") (pintype "power_in"))
    )
    (net (code "18") (name "unconnected-(U400A-VDD_MPU_MON-PadA2)") (class "Default")
      (node (ref "U400") (pin "A2") (pinfunction "VDD_MPU_MON_A2") (pintype "power_in+no_connect"))
    )
    (net (code "19") (name "unconnected-(U400A-VPP-PadM5)") (class "Default")
      (node (ref "U400") (pin "M5") (pinfunction "VPP_M5") (pintype "power_in+no_connect"))
    )
  )
)
